# 1551H-RS485_to_Neopixel_with_RJ45.net
KiCad netlist of a schematic drawn in EAGLE
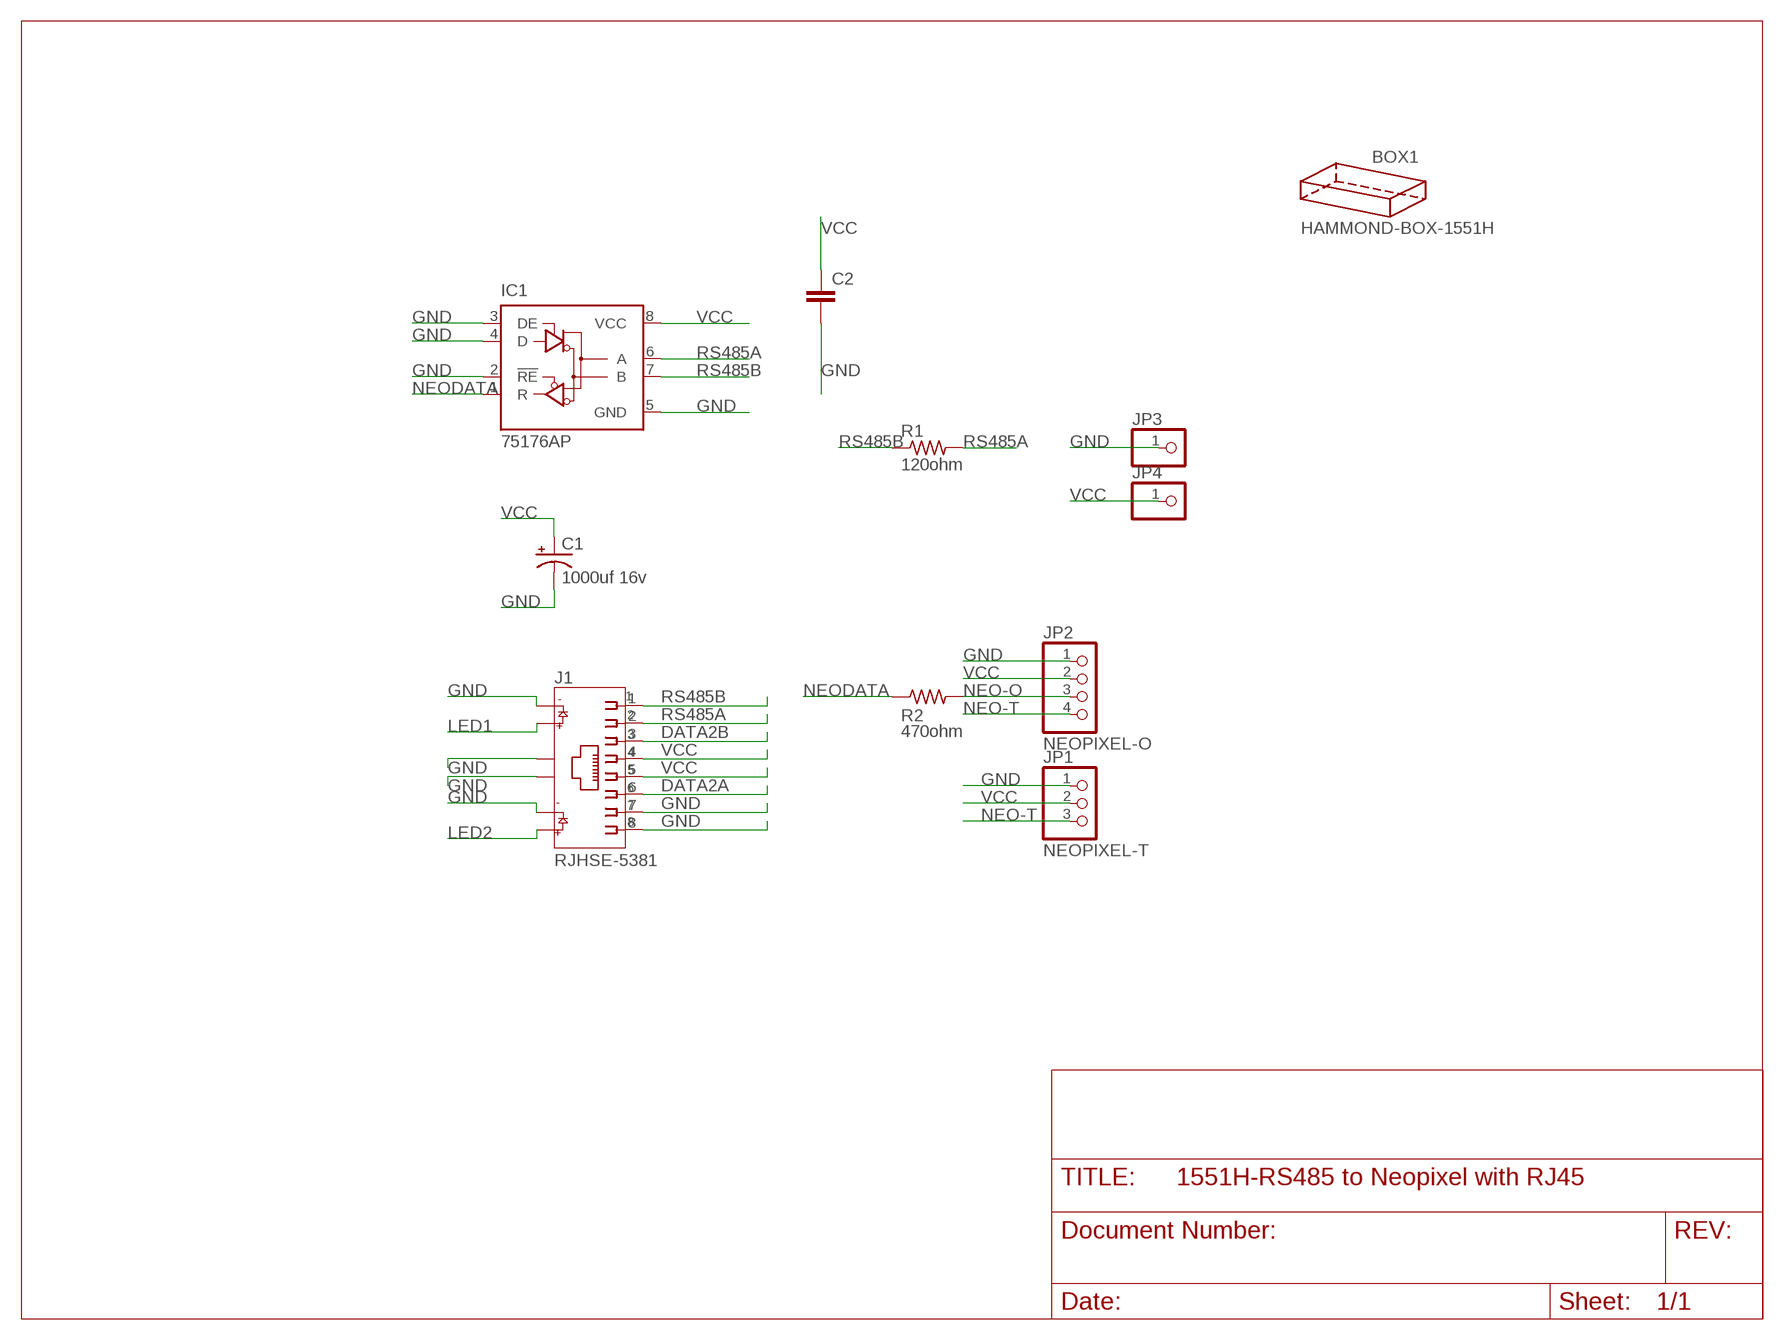
[diagram p0: schematic, sheet 1]

(export (version "E")
  (design (tool "Eeschema 10.0.6"))
  (components
    (comp (ref "BOX1")
      (value "HAMMOND-BOX-1551H")
      (footprint "eagle-import:1551H")
      (libsource (lib "eagle-import") (part "HAMMOND-BOX-1551H"))
    )
    (comp (ref "C1")
      (value "1000uf 16v")
      (footprint "eagle-import:CPOL-RADIAL-5MM-10MM")
      (libsource (lib "eagle-import") (part "1000UF-RADIAL-5MM-25V-20%"))
    )
    (comp (ref "C2")
      (value "CAPACITOR_0805_N")
      (footprint "eagle-import:RESC0805_N")
      (libsource (lib "eagle-import") (part "CAPACITOR_0805_N"))
    )
    (comp (ref "IC1")
      (value "75176AP")
      (footprint "eagle-import:DIL08")
      (libsource (lib "eagle-import") (part "75176AP"))
    )
    (comp (ref "J1")
      (value "RJHSE-5381")
      (footprint "eagle-import:AMPHENOL_RJHSE-5381")
      (fields (field (name "MF") "Amphenol ICC"))
      (libsource (lib "eagle-import") (part "RJHSE-5381"))
    )
    (comp (ref "JP1")
      (value "NEOPIXEL-T")
      (footprint "eagle-import:1X03")
      (libsource (lib "eagle-import") (part "PINHD-1X3"))
    )
    (comp (ref "JP2")
      (value "NEOPIXEL-O")
      (footprint "eagle-import:1X04")
      (libsource (lib "eagle-import") (part "PINHD-1X4"))
    )
    (comp (ref "JP3")
      (value "PINHD-1X1")
      (footprint "eagle-import:1X01")
      (libsource (lib "eagle-import") (part "PINHD-1X1"))
    )
    (comp (ref "JP4")
      (value "PINHD-1X1")
      (footprint "eagle-import:1X01")
      (libsource (lib "eagle-import") (part "PINHD-1X1"))
    )
    (comp (ref "R1")
      (value "120ohm")
      (footprint "eagle-import:R0805")
      (libsource (lib "eagle-import") (part "R-US_R0805"))
    )
    (comp (ref "R2")
      (value "470ohm")
      (footprint "eagle-import:R0805")
      (libsource (lib "eagle-import") (part "R-US_R0805"))
    )
  )
  (nets
    (net (code "1") (name "/DATA2A") (class "Default")
      (node (ref "J1") (pin "6") (pinfunction "6_6") (pintype "passive"))
    )
    (net (code "2") (name "/DATA2B") (class "Default")
      (node (ref "J1") (pin "3") (pinfunction "3_3") (pintype "passive"))
    )
    (net (code "3") (name "/GND") (class "Default")
      (node (ref "C1") (pin "-") (pinfunction "-_-") (pintype "passive"))
      (node (ref "C2") (pin "2") (pinfunction "2_2") (pintype "passive"))
      (node (ref "IC1") (pin "2") (pinfunction "~{RE}_2") (pintype "input"))
      (node (ref "IC1") (pin "3") (pinfunction "DE_3") (pintype "input"))
      (node (ref "IC1") (pin "4") (pinfunction "D_4") (pintype "input"))
      (node (ref "IC1") (pin "5") (pinfunction "GND_5") (pintype "power_in"))
      (node (ref "J1") (pin "11") (pinfunction "11_11") (pintype "passive"))
      (node (ref "J1") (pin "7") (pinfunction "7_7") (pintype "passive"))
      (node (ref "J1") (pin "8") (pinfunction "8_8") (pintype "passive"))
      (node (ref "J1") (pin "9") (pinfunction "9_9") (pintype "passive"))
      (node (ref "J1") (pin "S1") (pinfunction "S1_S1") (pintype "passive"))
      (node (ref "J1") (pin "S2") (pinfunction "S2_S2") (pintype "passive"))
      (node (ref "JP1") (pin "1") (pinfunction "1_1") (pintype "passive"))
      (node (ref "JP2") (pin "1") (pinfunction "1_1") (pintype "passive"))
      (node (ref "JP3") (pin "1") (pinfunction "1_1") (pintype "passive"))
    )
    (net (code "4") (name "/LED1") (class "Default")
      (node (ref "J1") (pin "10") (pinfunction "10_10") (pintype "passive"))
    )
    (net (code "5") (name "/LED2") (class "Default")
      (node (ref "J1") (pin "12") (pinfunction "12_12") (pintype "passive"))
    )
    (net (code "6") (name "/NEO-O") (class "Default")
      (node (ref "JP2") (pin "3") (pinfunction "3_3") (pintype "passive"))
      (node (ref "R2") (pin "2") (pinfunction "2_2") (pintype "passive"))
    )
    (net (code "7") (name "/NEO-T") (class "Default")
      (node (ref "JP1") (pin "3") (pinfunction "3_3") (pintype "passive"))
      (node (ref "JP2") (pin "4") (pinfunction "4_4") (pintype "passive"))
    )
    (net (code "8") (name "/NEODATA") (class "Default")
      (node (ref "IC1") (pin "1") (pinfunction "R_1") (pintype "input"))
      (node (ref "R2") (pin "1") (pinfunction "1_1") (pintype "passive"))
    )
    (net (code "9") (name "/RS485A") (class "Default")
      (node (ref "IC1") (pin "6") (pinfunction "A_6") (pintype "output"))
      (node (ref "J1") (pin "2") (pinfunction "2_2") (pintype "passive"))
      (node (ref "R1") (pin "2") (pinfunction "2_2") (pintype "passive"))
    )
    (net (code "10") (name "/RS485B") (class "Default")
      (node (ref "IC1") (pin "7") (pinfunction "B_7") (pintype "output"))
      (node (ref "J1") (pin "1") (pinfunction "1_1") (pintype "passive"))
      (node (ref "R1") (pin "1") (pinfunction "1_1") (pintype "passive"))
    )
    (net (code "11") (name "/VCC") (class "Default")
      (node (ref "C1") (pin "+") (pinfunction "+_+") (pintype "passive"))
      (node (ref "C2") (pin "1") (pinfunction "1_1") (pintype "passive"))
      (node (ref "IC1") (pin "8") (pinfunction "VCC_8") (pintype "power_in"))
      (node (ref "J1") (pin "4") (pinfunction "4_4") (pintype "passive"))
      (node (ref "J1") (pin "5") (pinfunction "5_5") (pintype "passive"))
      (node (ref "JP1") (pin "2") (pinfunction "2_2") (pintype "passive"))
      (node (ref "JP2") (pin "2") (pinfunction "2_2") (pintype "passive"))
      (node (ref "JP4") (pin "1") (pinfunction "1_1") (pintype "passive"))
    )
  )
)
